# 4_-_Position2Go_Baseband.net
KiCad netlist of a schematic drawn in Altium Designer
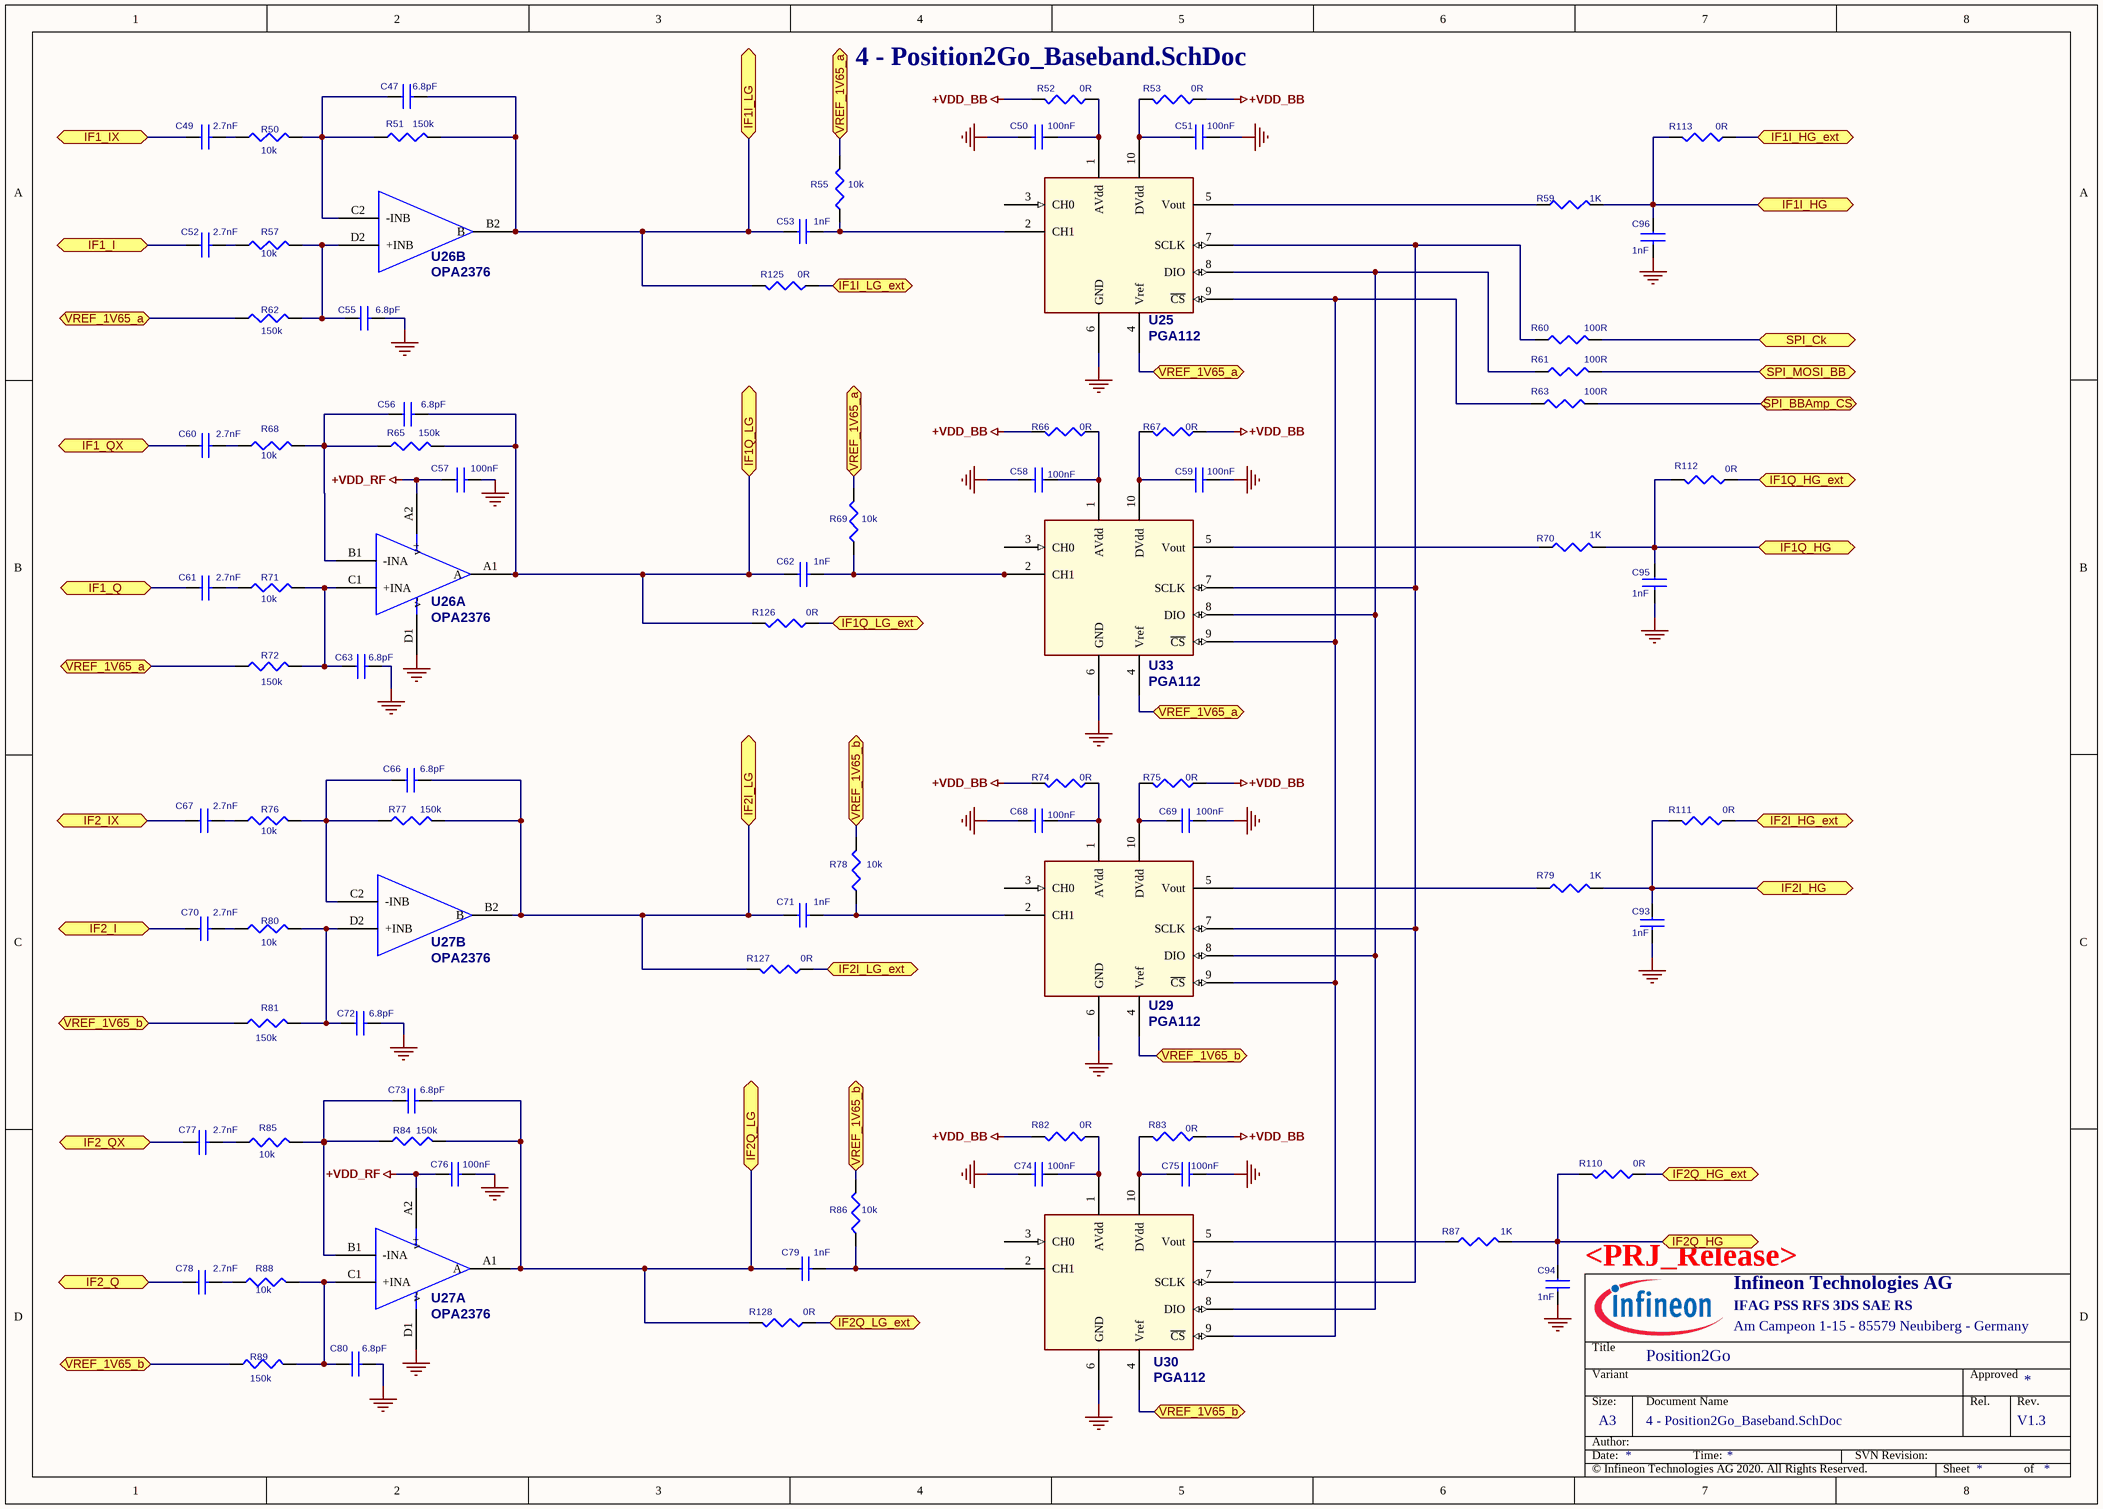
[diagram p0: 4 - Position2Go_Baseband.SchDoc]

(export (version "E")
  (design (tool "Eeschema 10.0.6"))
  (components
    (comp (ref "C47")
      (value "6.8pF")
      (footprint "C_0201")
      (fields (field (name "TOLERANCE") "0,5%") (field (name "VOLTAGE") "25V"))
      (libsource (lib "*") (part "15pF_Dup1"))
    )
    (comp (ref "C49")
      (value "2.7nF")
      (footprint "1206_40h")
      (fields (field (name "VOLTAGE") "50V") (field (name "TOLERANCE") "5%"))
      (libsource (lib "*") (part "220uF"))
    )
    (comp (ref "C50")
      (value "100nF")
      (footprint "C_0201")
      (fields (field (name "VOLTAGE") "50V") (field (name "TOLERANCE") "5%"))
      (libsource (lib "*") (part "100nF_Dup1"))
    )
    (comp (ref "C51")
      (value "100nF")
      (footprint "C_0201")
      (fields (field (name "VOLTAGE") "50V") (field (name "TOLERANCE") "5%"))
      (libsource (lib "*") (part "100nF_Dup1"))
    )
    (comp (ref "C52")
      (value "2.7nF")
      (footprint "1206_40h")
      (fields (field (name "VOLTAGE") "50V") (field (name "TOLERANCE") "5%"))
      (libsource (lib "*") (part "220uF"))
    )
    (comp (ref "C53")
      (value "1nF")
      (footprint "1206_40h")
      (fields (field (name "VOLTAGE") "50V") (field (name "TOLERANCE") "5%"))
      (libsource (lib "*") (part "220uF"))
    )
    (comp (ref "C55")
      (value "6.8pF")
      (footprint "C_0201")
      (fields (field (name "TOLERANCE") "0,5%") (field (name "VOLTAGE") "25V"))
      (libsource (lib "*") (part "15pF_Dup1"))
    )
    (comp (ref "C56")
      (value "6.8pF")
      (footprint "C_0201")
      (fields (field (name "TOLERANCE") "0,5%") (field (name "VOLTAGE") "25V"))
      (libsource (lib "*") (part "15pF_Dup1"))
    )
    (comp (ref "C57")
      (value "100nF")
      (footprint "C_0201")
      (fields (field (name "VOLTAGE") "50V") (field (name "TOLERANCE") "5%"))
      (libsource (lib "*") (part "100nF_Dup1"))
    )
    (comp (ref "C58")
      (value "100nF")
      (footprint "C_0201")
      (fields (field (name "VOLTAGE") "50V") (field (name "TOLERANCE") "5%"))
      (libsource (lib "*") (part "100nF_Dup1"))
    )
    (comp (ref "C59")
      (value "100nF")
      (footprint "C_0201")
      (fields (field (name "VOLTAGE") "50V") (field (name "TOLERANCE") "5%"))
      (libsource (lib "*") (part "100nF_Dup1"))
    )
    (comp (ref "C60")
      (value "2.7nF")
      (footprint "1206_40h")
      (fields (field (name "VOLTAGE") "50V") (field (name "TOLERANCE") "5%"))
      (libsource (lib "*") (part "220uF"))
    )
    (comp (ref "C61")
      (value "2.7nF")
      (footprint "1206_40h")
      (fields (field (name "VOLTAGE") "50V") (field (name "TOLERANCE") "5%"))
      (libsource (lib "*") (part "220uF"))
    )
    (comp (ref "C62")
      (value "1nF")
      (footprint "1206_40h")
      (fields (field (name "VOLTAGE") "50V") (field (name "TOLERANCE") "5%"))
      (libsource (lib "*") (part "220uF"))
    )
    (comp (ref "C63")
      (value "6.8pF")
      (footprint "C_0201")
      (fields (field (name "TOLERANCE") "0,5%") (field (name "VOLTAGE") "25V"))
      (libsource (lib "*") (part "15pF_Dup1"))
    )
    (comp (ref "C66")
      (value "6.8pF")
      (footprint "C_0201")
      (fields (field (name "TOLERANCE") "0,5%") (field (name "VOLTAGE") "25V"))
      (libsource (lib "*") (part "15pF_Dup1"))
    )
    (comp (ref "C67")
      (value "2.7nF")
      (footprint "1206_40h")
      (fields (field (name "VOLTAGE") "50V") (field (name "TOLERANCE") "5%"))
      (libsource (lib "*") (part "220uF"))
    )
    (comp (ref "C68")
      (value "100nF")
      (footprint "C_0201")
      (fields (field (name "VOLTAGE") "50V") (field (name "TOLERANCE") "5%"))
      (libsource (lib "*") (part "100nF_Dup1"))
    )
    (comp (ref "C69")
      (value "100nF")
      (footprint "C_0201")
      (fields (field (name "VOLTAGE") "50V") (field (name "TOLERANCE") "5%"))
      (libsource (lib "*") (part "100nF_Dup1"))
    )
    (comp (ref "C70")
      (value "2.7nF")
      (footprint "1206_40h")
      (fields (field (name "VOLTAGE") "50V") (field (name "TOLERANCE") "5%"))
      (libsource (lib "*") (part "220uF"))
    )
    (comp (ref "C71")
      (value "1nF")
      (footprint "1206_40h")
      (fields (field (name "VOLTAGE") "50V") (field (name "TOLERANCE") "5%"))
      (libsource (lib "*") (part "220uF"))
    )
    (comp (ref "C72")
      (value "6.8pF")
      (footprint "C_0201")
      (fields (field (name "TOLERANCE") "0,5%") (field (name "VOLTAGE") "25V"))
      (libsource (lib "*") (part "15pF_Dup1"))
    )
    (comp (ref "C73")
      (value "6.8pF")
      (footprint "C_0201")
      (fields (field (name "TOLERANCE") "0,5%") (field (name "VOLTAGE") "25V"))
      (libsource (lib "*") (part "15pF_Dup1"))
    )
    (comp (ref "C74")
      (value "100nF")
      (footprint "C_0201")
      (fields (field (name "VOLTAGE") "50V") (field (name "TOLERANCE") "5%"))
      (libsource (lib "*") (part "100nF_Dup1"))
    )
    (comp (ref "C75")
      (value "100nF")
      (footprint "C_0201")
      (fields (field (name "VOLTAGE") "50V") (field (name "TOLERANCE") "5%"))
      (libsource (lib "*") (part "100nF_Dup1"))
    )
    (comp (ref "C76")
      (value "100nF")
      (footprint "C_0201")
      (fields (field (name "VOLTAGE") "50V") (field (name "TOLERANCE") "5%"))
      (libsource (lib "*") (part "100nF_Dup1"))
    )
    (comp (ref "C77")
      (value "2.7nF")
      (footprint "1206_40h")
      (fields (field (name "VOLTAGE") "50V") (field (name "TOLERANCE") "5%"))
      (libsource (lib "*") (part "220uF"))
    )
    (comp (ref "C78")
      (value "2.7nF")
      (footprint "1206_40h")
      (fields (field (name "VOLTAGE") "50V") (field (name "TOLERANCE") "5%"))
      (libsource (lib "*") (part "220uF"))
    )
    (comp (ref "C79")
      (value "1nF")
      (footprint "1206_40h")
      (fields (field (name "VOLTAGE") "50V") (field (name "TOLERANCE") "5%"))
      (libsource (lib "*") (part "220uF"))
    )
    (comp (ref "C80")
      (value "6.8pF")
      (footprint "C_0201")
      (fields (field (name "TOLERANCE") "0,5%") (field (name "VOLTAGE") "25V"))
      (libsource (lib "*") (part "15pF_Dup1"))
    )
    (comp (ref "C93")
      (value "1nF")
      (footprint "C_0201")
      (fields (field (name "TOLERANCE") "10%") (field (name "VOLTAGE") "25V"))
      (libsource (lib "Position2Go_V1.1_08122017") (part "1nF"))
    )
    (comp (ref "C94")
      (value "1nF")
      (footprint "C_0201")
      (fields (field (name "TOLERANCE") "10%") (field (name "VOLTAGE") "25V"))
      (libsource (lib "Position2Go_V1.1_08122017") (part "1nF"))
    )
    (comp (ref "C95")
      (value "1nF")
      (footprint "C_0201")
      (fields (field (name "TOLERANCE") "10%") (field (name "VOLTAGE") "25V"))
      (libsource (lib "Position2Go_V1.1_08122017") (part "1nF"))
    )
    (comp (ref "C96")
      (value "1nF")
      (footprint "C_0201")
      (fields (field (name "TOLERANCE") "10%") (field (name "VOLTAGE") "25V"))
      (libsource (lib "Position2Go_V1.1_08122017") (part "1nF"))
    )
    (comp (ref "R50")
      (value "10k")
      (footprint "R_0201")
      (fields (field (name "TOLERANCE") "1%") (field (name "POWER") "0.063W"))
      (libsource (lib "*") (part "10K_Dup1"))
    )
    (comp (ref "R51")
      (value "150k")
      (footprint "R_0201")
      (fields (field (name "POWER") "0.063W") (field (name "TOLERANCE") "1%"))
      (libsource (lib "*") (part "100K"))
    )
    (comp (ref "R52")
      (value "0R")
      (footprint "R_0201")
      (fields (field (name "TOLERANCE") "1%") (field (name "POWER") "0.063W"))
      (libsource (lib "*") (part "0_Dup2"))
    )
    (comp (ref "R53")
      (value "0R")
      (footprint "R_0201")
      (fields (field (name "TOLERANCE") "1%") (field (name "POWER") "0.063W"))
      (libsource (lib "*") (part "0_Dup2"))
    )
    (comp (ref "R55")
      (value "10k")
      (footprint "R_0201")
      (fields (field (name "TOLERANCE") "1%") (field (name "POWER") "0.063W"))
      (libsource (lib "*") (part "10K_Dup1"))
    )
    (comp (ref "R57")
      (value "10k")
      (footprint "R_0201")
      (fields (field (name "TOLERANCE") "1%") (field (name "POWER") "0.063W"))
      (libsource (lib "*") (part "10K_Dup1"))
    )
    (comp (ref "R59")
      (value "1K")
      (footprint "R_0201")
      (fields (field (name "TOLERANCE") "1%") (field (name "POWER") "0.063W"))
      (libsource (lib "*") (part "10"))
    )
    (comp (ref "R60")
      (value "100R")
      (footprint "R_0201")
      (fields (field (name "TOLERANCE") "1%") (field (name "POWER") "0.063W"))
      (libsource (lib "*") (part "100"))
    )
    (comp (ref "R61")
      (value "100R")
      (footprint "R_0201")
      (fields (field (name "TOLERANCE") "1%") (field (name "POWER") "0.063W"))
      (libsource (lib "*") (part "100"))
    )
    (comp (ref "R62")
      (value "150k")
      (footprint "R_0201")
      (fields (field (name "POWER") "0.063W") (field (name "TOLERANCE") "1%"))
      (libsource (lib "*") (part "100K"))
    )
    (comp (ref "R63")
      (value "100R")
      (footprint "R_0201")
      (fields (field (name "TOLERANCE") "1%") (field (name "POWER") "0.063W"))
      (libsource (lib "*") (part "100"))
    )
    (comp (ref "R65")
      (value "150k")
      (footprint "R_0201")
      (fields (field (name "POWER") "0.063W") (field (name "TOLERANCE") "1%"))
      (libsource (lib "*") (part "100K"))
    )
    (comp (ref "R66")
      (value "0R")
      (footprint "R_0201")
      (fields (field (name "TOLERANCE") "1%") (field (name "POWER") "0.063W"))
      (libsource (lib "*") (part "0_Dup2"))
    )
    (comp (ref "R67")
      (value "0R")
      (footprint "R_0201")
      (fields (field (name "TOLERANCE") "1%") (field (name "POWER") "0.063W"))
      (libsource (lib "*") (part "0_Dup2"))
    )
    (comp (ref "R68")
      (value "10k")
      (footprint "R_0201")
      (fields (field (name "TOLERANCE") "1%") (field (name "POWER") "0.063W"))
      (libsource (lib "*") (part "10K_Dup1"))
    )
    (comp (ref "R69")
      (value "10k")
      (footprint "R_0201")
      (fields (field (name "TOLERANCE") "1%") (field (name "POWER") "0.063W"))
      (libsource (lib "*") (part "10K_Dup1"))
    )
    (comp (ref "R70")
      (value "1K")
      (footprint "R_0201")
      (fields (field (name "TOLERANCE") "1%") (field (name "POWER") "0.063W"))
      (libsource (lib "*") (part "10"))
    )
    (comp (ref "R71")
      (value "10k")
      (footprint "R_0201")
      (fields (field (name "TOLERANCE") "1%") (field (name "POWER") "0.063W"))
      (libsource (lib "*") (part "10K_Dup1"))
    )
    (comp (ref "R72")
      (value "150k")
      (footprint "R_0201")
      (fields (field (name "POWER") "0.063W") (field (name "TOLERANCE") "1%"))
      (libsource (lib "*") (part "100K"))
    )
    (comp (ref "R74")
      (value "0R")
      (footprint "R_0201")
      (fields (field (name "TOLERANCE") "1%") (field (name "POWER") "0.063W"))
      (libsource (lib "*") (part "0_Dup2"))
    )
    (comp (ref "R75")
      (value "0R")
      (footprint "R_0201")
      (fields (field (name "TOLERANCE") "1%") (field (name "POWER") "0.063W"))
      (libsource (lib "*") (part "0_Dup2"))
    )
    (comp (ref "R76")
      (value "10k")
      (footprint "R_0201")
      (fields (field (name "TOLERANCE") "1%") (field (name "POWER") "0.063W"))
      (libsource (lib "*") (part "10K_Dup1"))
    )
    (comp (ref "R77")
      (value "150k")
      (footprint "R_0201")
      (fields (field (name "POWER") "0.063W") (field (name "TOLERANCE") "1%"))
      (libsource (lib "*") (part "100K"))
    )
    (comp (ref "R78")
      (value "10k")
      (footprint "R_0201")
      (fields (field (name "TOLERANCE") "1%") (field (name "POWER") "0.063W"))
      (libsource (lib "*") (part "10K_Dup1"))
    )
    (comp (ref "R79")
      (value "1K")
      (footprint "R_0201")
      (fields (field (name "TOLERANCE") "1%") (field (name "POWER") "0.063W"))
      (libsource (lib "*") (part "10"))
    )
    (comp (ref "R80")
      (value "10k")
      (footprint "R_0201")
      (fields (field (name "TOLERANCE") "1%") (field (name "POWER") "0.063W"))
      (libsource (lib "*") (part "10K_Dup1"))
    )
    (comp (ref "R81")
      (value "150k")
      (footprint "R_0201")
      (fields (field (name "POWER") "0.063W") (field (name "TOLERANCE") "1%"))
      (libsource (lib "*") (part "100K"))
    )
    (comp (ref "R82")
      (value "0R")
      (footprint "R_0201")
      (fields (field (name "TOLERANCE") "1%") (field (name "POWER") "0.063W"))
      (libsource (lib "*") (part "0_Dup2"))
    )
    (comp (ref "R83")
      (value "0R")
      (footprint "R_0201")
      (fields (field (name "TOLERANCE") "1%") (field (name "POWER") "0.063W"))
      (libsource (lib "*") (part "0_Dup2"))
    )
    (comp (ref "R84")
      (value "150k")
      (footprint "R_0201")
      (fields (field (name "POWER") "0.063W") (field (name "TOLERANCE") "1%"))
      (libsource (lib "*") (part "100K"))
    )
    (comp (ref "R85")
      (value "10k")
      (footprint "R_0201")
      (fields (field (name "TOLERANCE") "1%") (field (name "POWER") "0.063W"))
      (libsource (lib "*") (part "10K_Dup1"))
    )
    (comp (ref "R86")
      (value "10k")
      (footprint "R_0201")
      (fields (field (name "TOLERANCE") "1%") (field (name "POWER") "0.063W"))
      (libsource (lib "*") (part "10K_Dup1"))
    )
    (comp (ref "R87")
      (value "1K")
      (footprint "R_0201")
      (fields (field (name "TOLERANCE") "1%") (field (name "POWER") "0.063W"))
      (libsource (lib "*") (part "10"))
    )
    (comp (ref "R88")
      (value "10k")
      (footprint "R_0201")
      (fields (field (name "TOLERANCE") "1%") (field (name "POWER") "0.063W"))
      (libsource (lib "*") (part "10K_Dup1"))
    )
    (comp (ref "R89")
      (value "150k")
      (footprint "R_0201")
      (fields (field (name "POWER") "0.063W") (field (name "TOLERANCE") "1%"))
      (libsource (lib "*") (part "100K"))
    )
    (comp (ref "R110")
      (value "0R")
      (footprint "R_0201")
      (fields (field (name "TOLERANCE") "1%") (field (name "POWER") "0.063W"))
      (libsource (lib "*") (part "0_Dup2"))
    )
    (comp (ref "R111")
      (value "0R")
      (footprint "R_0201")
      (fields (field (name "TOLERANCE") "1%") (field (name "POWER") "0.063W"))
      (libsource (lib "*") (part "0_Dup2"))
    )
    (comp (ref "R112")
      (value "0R")
      (footprint "R_0201")
      (fields (field (name "TOLERANCE") "1%") (field (name "POWER") "0.063W"))
      (libsource (lib "*") (part "0_Dup2"))
    )
    (comp (ref "R113")
      (value "0R")
      (footprint "R_0201")
      (fields (field (name "TOLERANCE") "1%") (field (name "POWER") "0.063W"))
      (libsource (lib "*") (part "0_Dup2"))
    )
    (comp (ref "R125")
      (value "0R")
      (footprint "R_0201")
      (fields (field (name "TOLERANCE") "1%") (field (name "POWER") "0.063W"))
      (libsource (lib "*") (part "0_Dup2"))
    )
    (comp (ref "R126")
      (value "0R")
      (footprint "R_0201")
      (fields (field (name "TOLERANCE") "1%") (field (name "POWER") "0.063W"))
      (libsource (lib "*") (part "0_Dup2"))
    )
    (comp (ref "R127")
      (value "0R")
      (footprint "R_0201")
      (fields (field (name "TOLERANCE") "1%") (field (name "POWER") "0.063W"))
      (libsource (lib "*") (part "0_Dup2"))
    )
    (comp (ref "R128")
      (value "0R")
      (footprint "R_0201")
      (fields (field (name "TOLERANCE") "1%") (field (name "POWER") "0.063W"))
      (libsource (lib "*") (part "0_Dup2"))
    )
    (comp (ref "U25") (value "PGA112") (footprint "DGS0010A_M") (libsource (lib "*") (part "PGA112")))
    (comp (ref "U26")
      (value "OPA2376")
      (footprint "OPA2376_DSBGA")
      (libsource (lib "*") (part "OPA2376_DSBGA_Dup1"))
    )
    (comp (ref "U27")
      (value "OPA2376")
      (footprint "OPA2376_DSBGA")
      (libsource (lib "*") (part "OPA2376_DSBGA_Dup1"))
    )
    (comp (ref "U29") (value "PGA112") (footprint "DGS0010A_M") (libsource (lib "*") (part "PGA112")))
    (comp (ref "U30") (value "PGA112") (footprint "DGS0010A_M") (libsource (lib "*") (part "PGA112")))
    (comp (ref "U33") (value "PGA112") (footprint "DGS0010A_M") (libsource (lib "*") (part "PGA112")))
  )
  (nets
    (net (code "1") (name "+VDD_BB") (class "Default")
      (node (ref "R52") (pin "2") (pinfunction "2_2") (pintype "passive"))
      (node (ref "R53") (pin "2") (pinfunction "2_2") (pintype "passive"))
      (node (ref "R66") (pin "2") (pinfunction "2_2") (pintype "passive"))
      (node (ref "R67") (pin "2") (pinfunction "2_2") (pintype "passive"))
      (node (ref "R74") (pin "2") (pinfunction "2_2") (pintype "passive"))
      (node (ref "R75") (pin "2") (pinfunction "2_2") (pintype "passive"))
      (node (ref "R82") (pin "2") (pinfunction "2_2") (pintype "passive"))
      (node (ref "R83") (pin "2") (pinfunction "2_2") (pintype "passive"))
    )
    (net (code "2") (name "+VDD_RF") (class "Default")
      (node (ref "C57") (pin "1") (pinfunction "1_1") (pintype "passive"))
      (node (ref "C76") (pin "1") (pinfunction "1_1") (pintype "passive"))
      (node (ref "U26") (pin "A2") (pinfunction "v+_A2") (pintype "power_in"))
      (node (ref "U27") (pin "A2") (pinfunction "v+_A2") (pintype "power_in"))
    )
    (net (code "3") (name "/IF1I_HG") (class "Default")
      (node (ref "C96") (pin "1") (pinfunction "1_1") (pintype "passive"))
      (node (ref "R113") (pin "2") (pinfunction "2_2") (pintype "passive"))
      (node (ref "R59") (pin "2") (pinfunction "2_2") (pintype "passive"))
    )
    (net (code "4") (name "/IF1I_HG_ext") (class "Default")
      (node (ref "R113") (pin "1") (pinfunction "1_1") (pintype "passive"))
    )
    (net (code "5") (name "/IF1I_LG") (class "Default")
      (node (ref "C47") (pin "2") (pinfunction "2_2") (pintype "passive"))
      (node (ref "C53") (pin "1") (pinfunction "1_1") (pintype "passive"))
      (node (ref "R125") (pin "2") (pinfunction "2_2") (pintype "passive"))
      (node (ref "R51") (pin "2") (pinfunction "2_2") (pintype "passive"))
      (node (ref "U26") (pin "B2") (pinfunction "B_B2") (pintype "passive"))
    )
    (net (code "6") (name "/IF1I_LG_ext") (class "Default")
      (node (ref "R125") (pin "1") (pinfunction "1_1") (pintype "passive"))
    )
    (net (code "7") (name "/IF1Q_HG") (class "Default")
      (node (ref "C95") (pin "1") (pinfunction "1_1") (pintype "passive"))
      (node (ref "R112") (pin "2") (pinfunction "2_2") (pintype "passive"))
      (node (ref "R70") (pin "2") (pinfunction "2_2") (pintype "passive"))
    )
    (net (code "8") (name "/IF1Q_HG_ext") (class "Default")
      (node (ref "R112") (pin "1") (pinfunction "1_1") (pintype "passive"))
    )
    (net (code "9") (name "/IF1Q_LG") (class "Default")
      (node (ref "C56") (pin "2") (pinfunction "2_2") (pintype "passive"))
      (node (ref "C62") (pin "1") (pinfunction "1_1") (pintype "passive"))
      (node (ref "R126") (pin "2") (pinfunction "2_2") (pintype "passive"))
      (node (ref "R65") (pin "2") (pinfunction "2_2") (pintype "passive"))
      (node (ref "U26") (pin "A1") (pinfunction "A_A1") (pintype "passive"))
    )
    (net (code "10") (name "/IF1Q_LG_ext") (class "Default")
      (node (ref "R126") (pin "1") (pinfunction "1_1") (pintype "passive"))
    )
    (net (code "11") (name "/IF1_I") (class "Default")
      (node (ref "C52") (pin "1") (pinfunction "1_1") (pintype "passive"))
    )
    (net (code "12") (name "/IF1_IX") (class "Default")
      (node (ref "C49") (pin "1") (pinfunction "1_1") (pintype "passive"))
    )
    (net (code "13") (name "/IF1_Q") (class "Default")
      (node (ref "C61") (pin "1") (pinfunction "1_1") (pintype "passive"))
    )
    (net (code "14") (name "/IF1_QX") (class "Default")
      (node (ref "C60") (pin "1") (pinfunction "1_1") (pintype "passive"))
    )
    (net (code "15") (name "/IF2I_HG") (class "Default")
      (node (ref "C93") (pin "1") (pinfunction "1_1") (pintype "passive"))
      (node (ref "R111") (pin "2") (pinfunction "2_2") (pintype "passive"))
      (node (ref "R79") (pin "2") (pinfunction "2_2") (pintype "passive"))
    )
    (net (code "16") (name "/IF2I_HG_ext") (class "Default")
      (node (ref "R111") (pin "1") (pinfunction "1_1") (pintype "passive"))
    )
    (net (code "17") (name "/IF2I_LG") (class "Default")
      (node (ref "C66") (pin "2") (pinfunction "2_2") (pintype "passive"))
      (node (ref "C71") (pin "1") (pinfunction "1_1") (pintype "passive"))
      (node (ref "R127") (pin "2") (pinfunction "2_2") (pintype "passive"))
      (node (ref "R77") (pin "2") (pinfunction "2_2") (pintype "passive"))
      (node (ref "U27") (pin "B2") (pinfunction "B_B2") (pintype "passive"))
    )
    (net (code "18") (name "/IF2I_LG_ext") (class "Default")
      (node (ref "R127") (pin "1") (pinfunction "1_1") (pintype "passive"))
    )
    (net (code "19") (name "/IF2Q_HG") (class "Default")
      (node (ref "C94") (pin "1") (pinfunction "1_1") (pintype "passive"))
      (node (ref "R110") (pin "2") (pinfunction "2_2") (pintype "passive"))
      (node (ref "R87") (pin "2") (pinfunction "2_2") (pintype "passive"))
    )
    (net (code "20") (name "/IF2Q_HG_ext") (class "Default")
      (node (ref "R110") (pin "1") (pinfunction "1_1") (pintype "passive"))
    )
    (net (code "21") (name "/IF2Q_LG") (class "Default")
      (node (ref "C73") (pin "2") (pinfunction "2_2") (pintype "passive"))
      (node (ref "C79") (pin "1") (pinfunction "1_1") (pintype "passive"))
      (node (ref "R128") (pin "2") (pinfunction "2_2") (pintype "passive"))
      (node (ref "R84") (pin "2") (pinfunction "2_2") (pintype "passive"))
      (node (ref "U27") (pin "A1") (pinfunction "A_A1") (pintype "passive"))
    )
    (net (code "22") (name "/IF2Q_LG_ext") (class "Default")
      (node (ref "R128") (pin "1") (pinfunction "1_1") (pintype "passive"))
    )
    (net (code "23") (name "/IF2_I") (class "Default")
      (node (ref "C70") (pin "1") (pinfunction "1_1") (pintype "passive"))
    )
    (net (code "24") (name "/IF2_IX") (class "Default")
      (node (ref "C67") (pin "1") (pinfunction "1_1") (pintype "passive"))
    )
    (net (code "25") (name "/IF2_Q") (class "Default")
      (node (ref "C78") (pin "1") (pinfunction "1_1") (pintype "passive"))
    )
    (net (code "26") (name "/IF2_QX") (class "Default")
      (node (ref "C77") (pin "1") (pinfunction "1_1") (pintype "passive"))
    )
    (net (code "27") (name "/SPI_BBAmp_CS") (class "Default")
      (node (ref "R63") (pin "2") (pinfunction "2_2") (pintype "passive"))
    )
    (net (code "28") (name "/SPI_Ck") (class "Default")
      (node (ref "R60") (pin "2") (pinfunction "2_2") (pintype "passive"))
    )
    (net (code "29") (name "/SPI_MOSI_BB") (class "Default")
      (node (ref "R61") (pin "2") (pinfunction "2_2") (pintype "passive"))
    )
    (net (code "30") (name "/VREF_1V65_a") (class "Default")
      (node (ref "R55") (pin "2") (pinfunction "2_2") (pintype "passive"))
      (node (ref "R62") (pin "2") (pinfunction "2_2") (pintype "passive"))
      (node (ref "R69") (pin "2") (pinfunction "2_2") (pintype "passive"))
      (node (ref "R72") (pin "2") (pinfunction "2_2") (pintype "passive"))
      (node (ref "U25") (pin "4") (pinfunction "Vref_4") (pintype "passive"))
      (node (ref "U33") (pin "4") (pinfunction "Vref_4") (pintype "passive"))
    )
    (net (code "31") (name "/VREF_1V65_b") (class "Default")
      (node (ref "R78") (pin "2") (pinfunction "2_2") (pintype "passive"))
      (node (ref "R81") (pin "2") (pinfunction "2_2") (pintype "passive"))
      (node (ref "R86") (pin "2") (pinfunction "2_2") (pintype "passive"))
      (node (ref "R89") (pin "2") (pinfunction "2_2") (pintype "passive"))
      (node (ref "U29") (pin "4") (pinfunction "Vref_4") (pintype "passive"))
      (node (ref "U30") (pin "4") (pinfunction "Vref_4") (pintype "passive"))
    )
    (net (code "32") (name "GND_POWER") (class "Default")
      (node (ref "C50") (pin "2") (pinfunction "2_2") (pintype "passive"))
      (node (ref "C51") (pin "2") (pinfunction "2_2") (pintype "passive"))
      (node (ref "C55") (pin "2") (pinfunction "2_2") (pintype "passive"))
      (node (ref "C57") (pin "2") (pinfunction "2_2") (pintype "passive"))
      (node (ref "C58") (pin "2") (pinfunction "2_2") (pintype "passive"))
      (node (ref "C59") (pin "2") (pinfunction "2_2") (pintype "passive"))
      (node (ref "C63") (pin "2") (pinfunction "2_2") (pintype "passive"))
      (node (ref "C68") (pin "2") (pinfunction "2_2") (pintype "passive"))
      (node (ref "C69") (pin "2") (pinfunction "2_2") (pintype "passive"))
      (node (ref "C72") (pin "2") (pinfunction "2_2") (pintype "passive"))
      (node (ref "C74") (pin "2") (pinfunction "2_2") (pintype "passive"))
      (node (ref "C75") (pin "2") (pinfunction "2_2") (pintype "passive"))
      (node (ref "C76") (pin "2") (pinfunction "2_2") (pintype "passive"))
      (node (ref "C80") (pin "2") (pinfunction "2_2") (pintype "passive"))
      (node (ref "C93") (pin "2") (pinfunction "2_2") (pintype "passive"))
      (node (ref "C94") (pin "2") (pinfunction "2_2") (pintype "passive"))
      (node (ref "C95") (pin "2") (pinfunction "2_2") (pintype "passive"))
      (node (ref "C96") (pin "2") (pinfunction "2_2") (pintype "passive"))
      (node (ref "U25") (pin "6") (pinfunction "GND_6") (pintype "power_in"))
      (node (ref "U26") (pin "D1") (pinfunction "v-_D1") (pintype "power_in"))
      (node (ref "U27") (pin "D1") (pinfunction "v-_D1") (pintype "power_in"))
      (node (ref "U29") (pin "6") (pinfunction "GND_6") (pintype "power_in"))
      (node (ref "U30") (pin "6") (pinfunction "GND_6") (pintype "power_in"))
      (node (ref "U33") (pin "6") (pinfunction "GND_6") (pintype "power_in"))
    )
    (net (code "33") (name "Net-(C49-Pad2)") (class "Default")
      (node (ref "C49") (pin "2") (pinfunction "2_2") (pintype "passive"))
      (node (ref "R50") (pin "1") (pinfunction "1_1") (pintype "passive"))
    )
    (net (code "34") (name "Net-(C52-Pad2)") (class "Default")
      (node (ref "C52") (pin "2") (pinfunction "2_2") (pintype "passive"))
      (node (ref "R57") (pin "1") (pinfunction "1_1") (pintype "passive"))
    )
    (net (code "35") (name "Net-(C60-Pad2)") (class "Default")
      (node (ref "C60") (pin "2") (pinfunction "2_2") (pintype "passive"))
      (node (ref "R68") (pin "1") (pinfunction "1_1") (pintype "passive"))
    )
    (net (code "36") (name "Net-(C61-Pad2)") (class "Default")
      (node (ref "C61") (pin "2") (pinfunction "2_2") (pintype "passive"))
      (node (ref "R71") (pin "1") (pinfunction "1_1") (pintype "passive"))
    )
    (net (code "37") (name "Net-(C67-Pad2)") (class "Default")
      (node (ref "C67") (pin "2") (pinfunction "2_2") (pintype "passive"))
      (node (ref "R76") (pin "1") (pinfunction "1_1") (pintype "passive"))
    )
    (net (code "38") (name "Net-(C70-Pad2)") (class "Default")
      (node (ref "C70") (pin "2") (pinfunction "2_2") (pintype "passive"))
      (node (ref "R80") (pin "1") (pinfunction "1_1") (pintype "passive"))
    )
    (net (code "39") (name "Net-(C77-Pad2)") (class "Default")
      (node (ref "C77") (pin "2") (pinfunction "2_2") (pintype "passive"))
      (node (ref "R85") (pin "1") (pinfunction "1_1") (pintype "passive"))
    )
    (net (code "40") (name "Net-(C78-Pad2)") (class "Default")
      (node (ref "C78") (pin "2") (pinfunction "2_2") (pintype "passive"))
      (node (ref "R88") (pin "1") (pinfunction "1_1") (pintype "passive"))
    )
    (net (code "41") (name "Net-(U25-AVdd)") (class "Default")
      (node (ref "C50") (pin "1") (pinfunction "1_1") (pintype "passive"))
      (node (ref "R52") (pin "1") (pinfunction "1_1") (pintype "passive"))
      (node (ref "U25") (pin "1") (pinfunction "AVdd_1") (pintype "power_in"))
    )
    (net (code "42") (name "Net-(U25-CH1)") (class "Default")
      (node (ref "C53") (pin "2") (pinfunction "2_2") (pintype "passive"))
      (node (ref "R55") (pin "1") (pinfunction "1_1") (pintype "passive"))
      (node (ref "U25") (pin "2") (pinfunction "CH1_2") (pintype "passive"))
    )
    (net (code "43") (name "Net-(U25-DIO)") (class "Default")
      (node (ref "R61") (pin "1") (pinfunction "1_1") (pintype "passive"))
      (node (ref "U25") (pin "8") (pinfunction "DIO_8") (pintype "bidirectional"))
      (node (ref "U29") (pin "8") (pinfunction "DIO_8") (pintype "bidirectional"))
      (node (ref "U30") (pin "8") (pinfunction "DIO_8") (pintype "bidirectional"))
      (node (ref "U33") (pin "8") (pinfunction "DIO_8") (pintype "bidirectional"))
    )
    (net (code "44") (name "Net-(U25-DVdd)") (class "Default")
      (node (ref "C51") (pin "1") (pinfunction "1_1") (pintype "passive"))
      (node (ref "R53") (pin "1") (pinfunction "1_1") (pintype "passive"))
      (node (ref "U25") (pin "10") (pinfunction "DVdd_10") (pintype "power_in"))
    )
    (net (code "45") (name "Net-(U25-SCLK)") (class "Default")
      (node (ref "R60") (pin "1") (pinfunction "1_1") (pintype "passive"))
      (node (ref "U25") (pin "7") (pinfunction "SCLK_7") (pintype "bidirectional"))
      (node (ref "U29") (pin "7") (pinfunction "SCLK_7") (pintype "bidirectional"))
      (node (ref "U30") (pin "7") (pinfunction "SCLK_7") (pintype "bidirectional"))
      (node (ref "U33") (pin "7") (pinfunction "SCLK_7") (pintype "bidirectional"))
    )
    (net (code "46") (name "Net-(U25-Vout)") (class "Default")
      (node (ref "R59") (pin "1") (pinfunction "1_1") (pintype "passive"))
      (node (ref "U25") (pin "5") (pinfunction "Vout_5") (pintype "passive"))
    )
    (net (code "47") (name "Net-(U25-~{CS})") (class "Default")
      (node (ref "R63") (pin "1") (pinfunction "1_1") (pintype "passive"))
      (node (ref "U25") (pin "9") (pinfunction "~{CS}_9") (pintype "bidirectional"))
      (node (ref "U29") (pin "9") (pinfunction "~{CS}_9") (pintype "bidirectional"))
      (node (ref "U30") (pin "9") (pinfunction "~{CS}_9") (pintype "bidirectional"))
      (node (ref "U33") (pin "9") (pinfunction "~{CS}_9") (pintype "bidirectional"))
    )
    (net (code "48") (name "Net-(U26A-+INA)") (class "Default")
      (node (ref "C63") (pin "1") (pinfunction "1_1") (pintype "passive"))
      (node (ref "R71") (pin "2") (pinfunction "2_2") (pintype "passive"))
      (node (ref "R72") (pin "1") (pinfunction "1_1") (pintype "passive"))
      (node (ref "U26") (pin "C1") (pinfunction "+INA_C1") (pintype "passive"))
    )
    (net (code "49") (name "Net-(U26A--INA)") (class "Default")
      (node (ref "C56") (pin "1") (pinfunction "1_1") (pintype "passive"))
      (node (ref "R65") (pin "1") (pinfunction "1_1") (pintype "passive"))
      (node (ref "R68") (pin "2") (pinfunction "2_2") (pintype "passive"))
      (node (ref "U26") (pin "B1") (pinfunction "-INA_B1") (pintype "passive"))
    )
    (net (code "50") (name "Net-(U26B-+INB)") (class "Default")
      (node (ref "C55") (pin "1") (pinfunction "1_1") (pintype "passive"))
      (node (ref "R57") (pin "2") (pinfunction "2_2") (pintype "passive"))
      (node (ref "R62") (pin "1") (pinfunction "1_1") (pintype "passive"))
      (node (ref "U26") (pin "D2") (pinfunction "+INB_D2") (pintype "passive"))
    )
    (net (code "51") (name "Net-(U26B--INB)") (class "Default")
      (node (ref "C47") (pin "1") (pinfunction "1_1") (pintype "passive"))
      (node (ref "R50") (pin "2") (pinfunction "2_2") (pintype "passive"))
      (node (ref "R51") (pin "1") (pinfunction "1_1") (pintype "passive"))
      (node (ref "U26") (pin "C2") (pinfunction "-INB_C2") (pintype "passive"))
    )
    (net (code "52") (name "Net-(U27A-+INA)") (class "Default")
      (node (ref "C80") (pin "1") (pinfunction "1_1") (pintype "passive"))
      (node (ref "R88") (pin "2") (pinfunction "2_2") (pintype "passive"))
      (node (ref "R89") (pin "1") (pinfunction "1_1") (pintype "passive"))
      (node (ref "U27") (pin "C1") (pinfunction "+INA_C1") (pintype "passive"))
    )
    (net (code "53") (name "Net-(U27A--INA)") (class "Default")
      (node (ref "C73") (pin "1") (pinfunction "1_1") (pintype "passive"))
      (node (ref "R84") (pin "1") (pinfunction "1_1") (pintype "passive"))
      (node (ref "R85") (pin "2") (pinfunction "2_2") (pintype "passive"))
      (node (ref "U27") (pin "B1") (pinfunction "-INA_B1") (pintype "passive"))
    )
    (net (code "54") (name "Net-(U27B-+INB)") (class "Default")
      (node (ref "C72") (pin "1") (pinfunction "1_1") (pintype "passive"))
      (node (ref "R80") (pin "2") (pinfunction "2_2") (pintype "passive"))
      (node (ref "R81") (pin "1") (pinfunction "1_1") (pintype "passive"))
      (node (ref "U27") (pin "D2") (pinfunction "+INB_D2") (pintype "passive"))
    )
    (net (code "55") (name "Net-(U27B--INB)") (class "Default")
      (node (ref "C66") (pin "1") (pinfunction "1_1") (pintype "passive"))
      (node (ref "R76") (pin "2") (pinfunction "2_2") (pintype "passive"))
      (node (ref "R77") (pin "1") (pinfunction "1_1") (pintype "passive"))
      (node (ref "U27") (pin "C2") (pinfunction "-INB_C2") (pintype "passive"))
    )
    (net (code "56") (name "Net-(U29-AVdd)") (class "Default")
      (node (ref "C68") (pin "1") (pinfunction "1_1") (pintype "passive"))
      (node (ref "R74") (pin "1") (pinfunction "1_1") (pintype "passive"))
      (node (ref "U29") (pin "1") (pinfunction "AVdd_1") (pintype "power_in"))
    )
    (net (code "57") (name "Net-(U29-CH1)") (class "Default")
      (node (ref "C71") (pin "2") (pinfunction "2_2") (pintype "passive"))
      (node (ref "R78") (pin "1") (pinfunction "1_1") (pintype "passive"))
      (node (ref "U29") (pin "2") (pinfunction "CH1_2") (pintype "passive"))
    )
    (net (code "58") (name "Net-(U29-DVdd)") (class "Default")
      (node (ref "C69") (pin "1") (pinfunction "1_1") (pintype "passive"))
      (node (ref "R75") (pin "1") (pinfunction "1_1") (pintype "passive"))
      (node (ref "U29") (pin "10") (pinfunction "DVdd_10") (pintype "power_in"))
    )
    (net (code "59") (name "Net-(U29-Vout)") (class "Default")
      (node (ref "R79") (pin "1") (pinfunction "1_1") (pintype "passive"))
      (node (ref "U29") (pin "5") (pinfunction "Vout_5") (pintype "passive"))
    )
    (net (code "60") (name "Net-(U30-AVdd)") (class "Default")
      (node (ref "C74") (pin "1") (pinfunction "1_1") (pintype "passive"))
      (node (ref "R82") (pin "1") (pinfunction "1_1") (pintype "passive"))
      (node (ref "U30") (pin "1") (pinfunction "AVdd_1") (pintype "power_in"))
    )
    (net (code "61") (name "Net-(U30-CH1)") (class "Default")
      (node (ref "C79") (pin "2") (pinfunction "2_2") (pintype "passive"))
      (node (ref "R86") (pin "1") (pinfunction "1_1") (pintype "passive"))
      (node (ref "U30") (pin "2") (pinfunction "CH1_2") (pintype "passive"))
    )
    (net (code "62") (name "Net-(U30-DVdd)") (class "Default")
      (node (ref "C75") (pin "1") (pinfunction "1_1") (pintype "passive"))
      (node (ref "R83") (pin "1") (pinfunction "1_1") (pintype "passive"))
      (node (ref "U30") (pin "10") (pinfunction "DVdd_10") (pintype "power_in"))
    )
    (net (code "63") (name "Net-(U30-Vout)") (class "Default")
      (node (ref "R87") (pin "1") (pinfunction "1_1") (pintype "passive"))
      (node (ref "U30") (pin "5") (pinfunction "Vout_5") (pintype "passive"))
    )
    (net (code "64") (name "Net-(U33-AVdd)") (class "Default")
      (node (ref "C58") (pin "1") (pinfunction "1_1") (pintype "passive"))
      (node (ref "R66") (pin "1") (pinfunction "1_1") (pintype "passive"))
      (node (ref "U33") (pin "1") (pinfunction "AVdd_1") (pintype "power_in"))
    )
    (net (code "65") (name "Net-(U33-CH1)") (class "Default")
      (node (ref "C62") (pin "2") (pinfunction "2_2") (pintype "passive"))
      (node (ref "R69") (pin "1") (pinfunction "1_1") (pintype "passive"))
      (node (ref "U33") (pin "2") (pinfunction "CH1_2") (pintype "passive"))
    )
    (net (code "66") (name "Net-(U33-DVdd)") (class "Default")
      (node (ref "C59") (pin "1") (pinfunction "1_1") (pintype "passive"))
      (node (ref "R67") (pin "1") (pinfunction "1_1") (pintype "passive"))
      (node (ref "U33") (pin "10") (pinfunction "DVdd_10") (pintype "power_in"))
    )
    (net (code "67") (name "Net-(U33-Vout)") (class "Default")
      (node (ref "R70") (pin "1") (pinfunction "1_1") (pintype "passive"))
      (node (ref "U33") (pin "5") (pinfunction "Vout_5") (pintype "passive"))
    )
    (net (code "68") (name "unconnected-(U25-CH0-Pad3)") (class "Default")
      (node (ref "U25") (pin "3") (pinfunction "CH0_3") (pintype "input"))
    )
    (net (code "69") (name "unconnected-(U29-CH0-Pad3)") (class "Default")
      (node (ref "U29") (pin "3") (pinfunction "CH0_3") (pintype "input"))
    )
    (net (code "70") (name "unconnected-(U30-CH0-Pad3)") (class "Default")
      (node (ref "U30") (pin "3") (pinfunction "CH0_3") (pintype "input"))
    )
    (net (code "71") (name "unconnected-(U33-CH0-Pad3)") (class "Default")
      (node (ref "U33") (pin "3") (pinfunction "CH0_3") (pintype "input"))
    )
  )
)
